# Power.net
KiCad netlist of a schematic drawn in Altium Designer
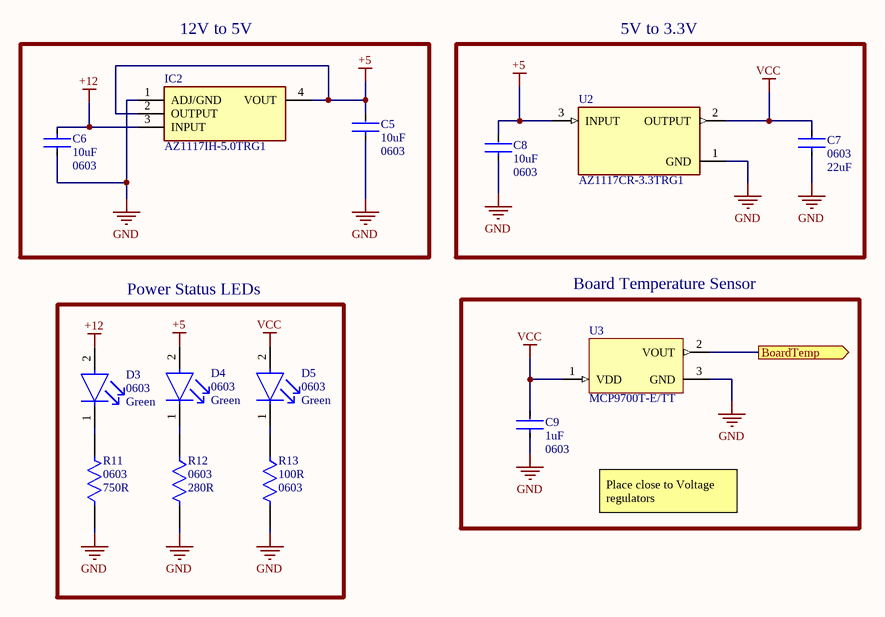
[diagram p0: Power.SchDoc]

(export (version "E")
  (design (tool "Eeschema 10.0.6"))
  (components
    (comp (ref "C5")
      (value "CL10A106MQ8NNNC")
      (footprint "FP-CL10-IPC_C")
      (description "Cap Ceramic 10uF 6.3V X5R ±20% Pad SMD 0603 +85°C T/R")
      (fields
        (field (name "CAPACITANCE") "10uF")
        (field (name "CASE/PACKAGE") "0603")
        (field (name "VOLTAGE") "6.3V")
        (field (name "TOLERANCE") "20%")
      )
      (libsource (lib "Altium Content Vault") (part "b4654b650e69147ec39a6b967a45e02"))
    )
    (comp (ref "C6")
      (value "CL10A106MQ8NNNC")
      (footprint "FP-CL10-IPC_C")
      (description "Cap Ceramic 10uF 6.3V X5R ±20% Pad SMD 0603 +85°C T/R")
      (fields
        (field (name "CAPACITANCE") "10uF")
        (field (name "CASE/PACKAGE") "0603")
        (field (name "VOLTAGE") "6.3V")
        (field (name "TOLERANCE") "20%")
      )
      (libsource (lib "Altium Content Vault") (part "b4654b650e69147ec39a6b967a45e02"))
    )
    (comp (ref "C7")
      (value "GRM188R60G226MEA0D")
      (footprint "FP-GRM188-0_2-MFG")
      (description "Chip Multilayer Ceramic Capacitors for General Purpose, 0603, 22uF, X5R, 15%, 20%, 4V")
      (fields
        (field (name "CASE/PACKAGE") "0603")
        (field (name "VOLTAGE") "4V")
        (field (name "TOLERANCE") "20%")
        (field (name "CAPACITANCE") "22uF")
      )
      (libsource (lib "Altium Content Vault") (part "11868f565c42a9108669ba33697ecf6"))
    )
    (comp (ref "C8")
      (value "CL10A106MQ8NNNC")
      (footprint "FP-CL10-IPC_C")
      (description "Cap Ceramic 10uF 6.3V X5R ±20% Pad SMD 0603 +85°C T/R")
      (fields
        (field (name "CAPACITANCE") "10uF")
        (field (name "CASE/PACKAGE") "0603")
        (field (name "VOLTAGE") "6.3V")
        (field (name "TOLERANCE") "20%")
      )
      (libsource (lib "Altium Content Vault") (part "b4654b650e69147ec39a6b967a45e02"))
    )
    (comp (ref "C9")
      (value "CL10A105KO8NNNC")
      (footprint "FP-CL10-IPC_A")
      (description "Cap Ceramic 1uF 16V X5R ±10% Pad SMD 0603 +85°C T/R")
      (fields
        (field (name "CAPACITANCE") "1uF")
        (field (name "CASE CODE (IMPERIAL)") "0603")
        (field (name "TOLERANCE") "10%")
        (field (name "VOLTAGE") "16V")
      )
      (libsource (lib "Altium Content Vault") (part "b4654b650e69147ec39a6b967a45e02"))
    )
    (comp (ref "D3")
      (value "12V")
      (footprint "FP-LTST-C190KGKT-MFG")
      (description "LED GREEN CLEAR CHIP SMD")
      (fields (field (name "CASE CODE (IMPERIAL)") "0603") (field (name "COLOR") "Green"))
      (libsource (lib "Altium Content Vault") (part "8706943c75ba83719d021d2fdc84c58"))
    )
    (comp (ref "D4")
      (value "5V")
      (footprint "FP-LTST-C190KGKT-MFG")
      (description "LED GREEN CLEAR CHIP SMD")
      (fields (field (name "CASE CODE (IMPERIAL)") "0603") (field (name "COLOR") "Green"))
      (libsource (lib "Altium Content Vault") (part "8706943c75ba83719d021d2fdc84c58"))
    )
    (comp (ref "D5")
      (value "3V3")
      (footprint "FP-LTST-C190KGKT-MFG")
      (description "LED GREEN CLEAR CHIP SMD")
      (fields (field (name "CASE CODE (IMPERIAL)") "0603") (field (name "COLOR") "Green"))
      (libsource (lib "Altium Content Vault") (part "8706943c75ba83719d021d2fdc84c58"))
    )
    (comp (ref "IC2")
      (value "AZ1117IH-5.0TRG1")
      (footprint "SOT230P700X170-4N")
      (description "Integrated Circuit")
      (fields (field (name "MOUSER PART NUMBER") "621-AZ1117IH-5.0TRG1"))
      (libsource (lib "WiCAN_lib") (part "AZ1117IH-5.0TRG1"))
    )
    (comp (ref "R11")
      (value "ESR03EZPJ751")
      (footprint "FP-ESR03-IPC_B")
      (description "750Ω ±5% 0.25W 0603 Anti-Surge Chip Resistor AEC-Q200")
      (fields
        (field (name "CASE/PACKAGE") "0603")
        (field (name "RESISTANCE") "750R")
        (field (name "TOLERANCE") "5%")
      )
      (libsource (lib "Altium Content Vault") (part "1029c3af85768c4190bb7ad29bc67b5"))
    )
    (comp (ref "R12")
      (value "RMCF0603FT280R")
      (footprint "FP-RMCF0603-MFG")
      (description "280Ω ±1% 0.1W 0603 Thick Film Chip Resistor AEC-Q200 compliant")
      (fields
        (field (name "CASE/PACKAGE") "0603")
        (field (name "TOLERANCE") "1%")
        (field (name "RESISTANCE") "280R")
      )
      (libsource (lib "Altium Content Vault") (part "1029c3af85768c4190bb7ad29bc67b5"))
    )
    (comp (ref "R13")
      (value "AC0603FR-10100RL")
      (footprint "FP-AC0603-IPC_A")
      (description "RES 100Ω 1.00% 0.1W 0603")
      (fields
        (field (name "TOLERANCE") "1%")
        (field (name "RESISTANCE") "100R")
        (field (name "CASE/PACKAGE") "0603")
      )
      (libsource (lib "Altium Content Vault") (part "1029c3af85768c4190bb7ad29bc67b5"))
    )
    (comp (ref "U2")
      (value "AZ1117CR-3.3TRG1")
      (footprint "FP-SOT89-MFG")
      (description "IC REG LINEAR 3.3V 800MA SOT89")
      (fields
        (field (name "OCTOPART") "https://octopart.com/az1117cr-3.3trg1-diodes+inc.-30954805")
        (field (name "MANUFACTURER") "Diodes Inc.")
      )
      (libsource (lib "Altium Content Vault") (part "80dc4d5e0c5bf011f486f511683fde3"))
    )
    (comp (ref "U3")
      (value "MCP9700T-E/TT")
      (footprint "SOT-23-TT3_M")
      (description "Low-Power Linear Active Thermistor IC, 3-Pin SOT-23, Extended Temperature, Tape and Reel")
      (libsource (lib "Altium Content Vault") (part "SEN-TEMP-MCP9700-3"))
    )
  )
  (nets
    (net (code "1") (name "+5") (class "Default")
      (node (ref "C5") (pin "2") (pinfunction "2_2") (pintype "passive"))
      (node (ref "C8") (pin "2") (pinfunction "2_2") (pintype "passive"))
      (node (ref "D4") (pin "2") (pinfunction "A_2") (pintype "passive"))
      (node (ref "IC2") (pin "2") (pinfunction "OUTPUT_2") (pintype "passive"))
      (node (ref "IC2") (pin "4") (pinfunction "VOUT_4") (pintype "passive"))
      (node (ref "U2") (pin "3") (pinfunction "INPUT_3") (pintype "input"))
    )
    (net (code "2") (name "+12") (class "Default")
      (node (ref "C6") (pin "1") (pinfunction "1_1") (pintype "passive"))
      (node (ref "D3") (pin "2") (pinfunction "A_2") (pintype "passive"))
      (node (ref "IC2") (pin "3") (pinfunction "INPUT_3") (pintype "passive"))
    )
    (net (code "3") (name "/BoardTemp") (class "Default")
      (node (ref "U3") (pin "2") (pinfunction "VOUT_2") (pintype "output"))
    )
    (net (code "4") (name "GND") (class "Default")
      (node (ref "C5") (pin "1") (pinfunction "1_1") (pintype "passive"))
      (node (ref "C6") (pin "2") (pinfunction "2_2") (pintype "passive"))
      (node (ref "C7") (pin "1") (pinfunction "1_1") (pintype "passive"))
      (node (ref "C8") (pin "1") (pinfunction "1_1") (pintype "passive"))
      (node (ref "C9") (pin "1") (pinfunction "1_1") (pintype "passive"))
      (node (ref "IC2") (pin "1") (pinfunction "ADJ/GND_1") (pintype "passive"))
      (node (ref "R11") (pin "1") (pinfunction "1_1") (pintype "passive"))
      (node (ref "R12") (pin "2") (pinfunction "2_2") (pintype "passive"))
      (node (ref "R13") (pin "2") (pinfunction "2_2") (pintype "passive"))
      (node (ref "U2") (pin "1") (pinfunction "GND_1") (pintype "power_in"))
      (node (ref "U3") (pin "3") (pinfunction "GND_3") (pintype "power_in"))
    )
    (net (code "5") (name "Net-(D3-C)") (class "Default")
      (node (ref "D3") (pin "1") (pinfunction "C_1") (pintype "passive"))
      (node (ref "R11") (pin "2") (pinfunction "2_2") (pintype "passive"))
    )
    (net (code "6") (name "Net-(D4-C)") (class "Default")
      (node (ref "D4") (pin "1") (pinfunction "C_1") (pintype "passive"))
      (node (ref "R12") (pin "1") (pinfunction "1_1") (pintype "passive"))
    )
    (net (code "7") (name "Net-(D5-C)") (class "Default")
      (node (ref "D5") (pin "1") (pinfunction "C_1") (pintype "passive"))
      (node (ref "R13") (pin "1") (pinfunction "1_1") (pintype "passive"))
    )
    (net (code "8") (name "VCC") (class "Default")
      (node (ref "C7") (pin "2") (pinfunction "2_2") (pintype "passive"))
      (node (ref "C9") (pin "2") (pinfunction "2_2") (pintype "passive"))
      (node (ref "D5") (pin "2") (pinfunction "A_2") (pintype "passive"))
      (node (ref "U2") (pin "2") (pinfunction "OUTPUT_2") (pintype "output"))
      (node (ref "U3") (pin "1") (pinfunction "VDD_1") (pintype "input"))
    )
  )
)
